# usb-cuter.net
KiCad netlist of a schematic drawn in Altium Designer
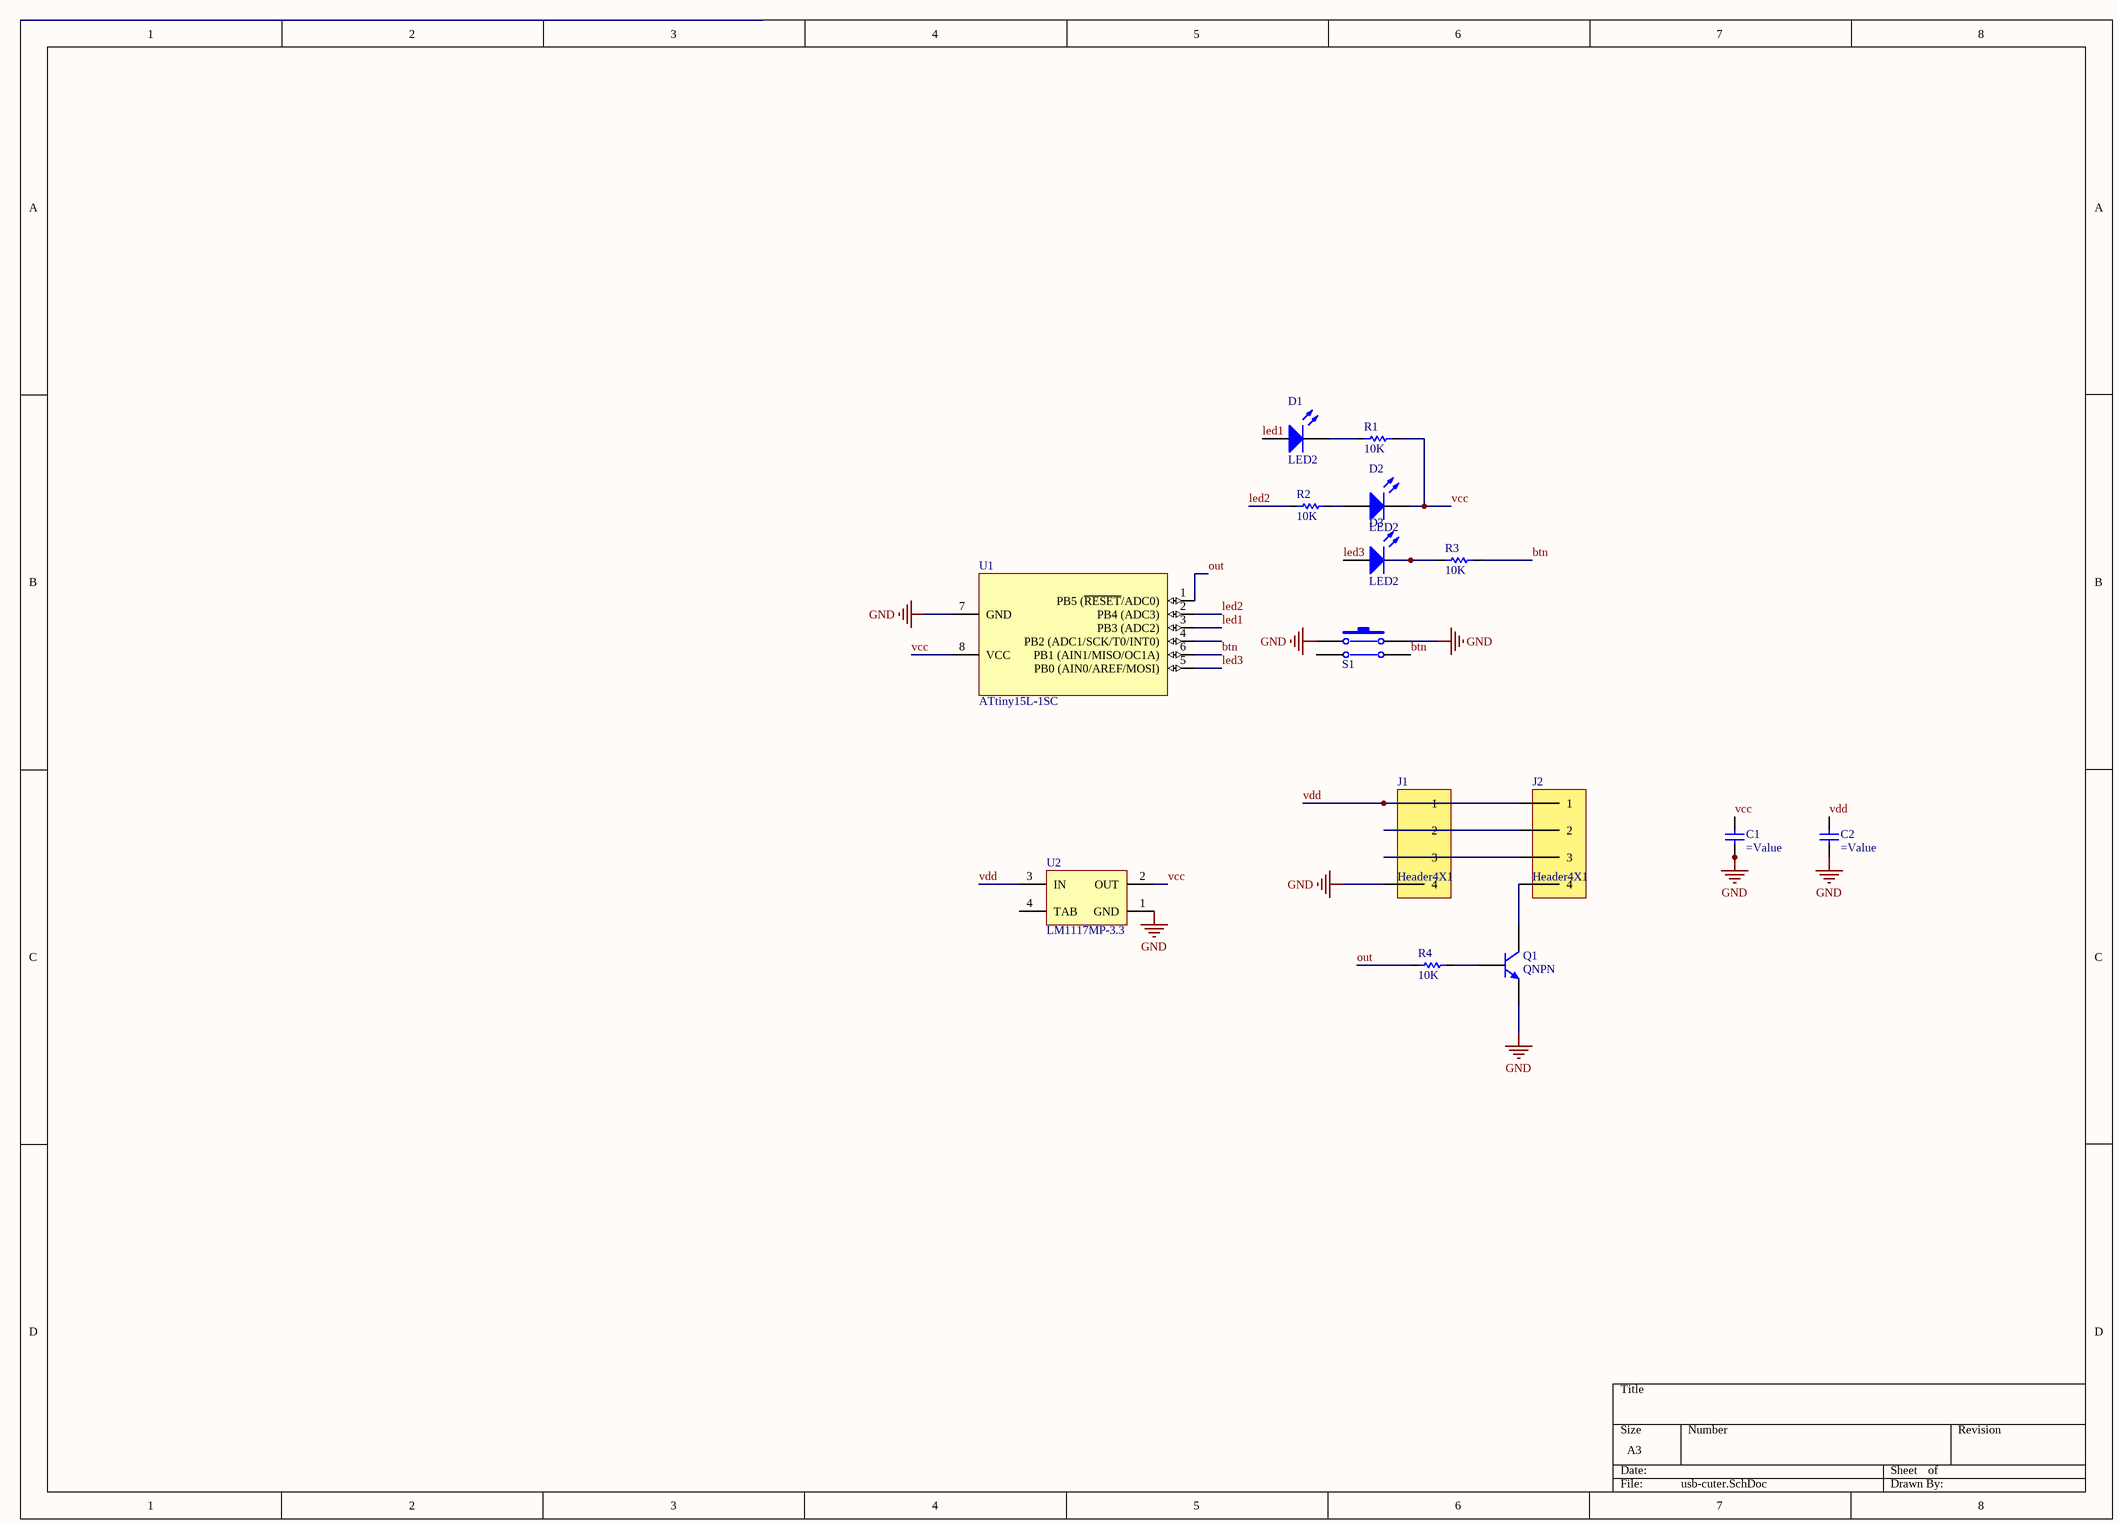
[diagram p0: usb-cuter.SchDoc]

(export (version "E")
  (design (tool "Eeschema 10.0.6"))
  (components
    (comp (ref "C1")
      (value "~")
      (footprint "CAP 0805")
      (description "Capacitor")
      (libsource (lib "AltiumLib1") (part "Capacitor"))
    )
    (comp (ref "C2")
      (value "~")
      (footprint "CAP 0805")
      (description "Capacitor")
      (libsource (lib "AltiumLib1") (part "Capacitor"))
    )
    (comp (ref "D1")
      (value "LED2")
      (footprint "3.2X1.6X1.1")
      (description "Typical RED, GREEN, YELLOW, AMBER GaAs LED")
      (fields (field (name "PUBLISHER") "Altium Limited"))
      (libsource (lib "Miscellaneous Devices") (part "LED2"))
    )
    (comp (ref "D2")
      (value "LED2")
      (footprint "3.2X1.6X1.1")
      (description "Typical RED, GREEN, YELLOW, AMBER GaAs LED")
      (fields (field (name "PUBLISHER") "Altium Limited"))
      (libsource (lib "Miscellaneous Devices") (part "LED2"))
    )
    (comp (ref "D3")
      (value "LED2")
      (footprint "3.2X1.6X1.1")
      (description "Typical RED, GREEN, YELLOW, AMBER GaAs LED")
      (fields (field (name "PUBLISHER") "Altium Limited"))
      (libsource (lib "Miscellaneous Devices") (part "LED2"))
    )
    (comp (ref "J1")
      (value "Header4X1")
      (footprint "HEADER 4X1")
      (libsource (lib "AltiumLib1") (part "Header4X1"))
    )
    (comp (ref "J2")
      (value "Header4X1")
      (footprint "HEADER 4X1")
      (libsource (lib "AltiumLib1") (part "Header4X1"))
    )
    (comp (ref "Q1")
      (value "QNPN")
      (footprint "SOT-23B_L")
      (description "NPN Bipolar Transistor")
      (fields (field (name "PUBLISHER") "Altium Limited"))
      (libsource (lib "Miscellaneous Devices") (part "QNPN"))
    )
    (comp (ref "R1")
      (value "10K")
      (footprint "RES 0805 (2012X06L)")
      (description "Resistor")
      (fields (field (name "TOLERANCE") "5%") (field (name "POWER") "1/4 W"))
      (libsource (lib "AltiumLib1") (part "Resistor"))
    )
    (comp (ref "R2")
      (value "10K")
      (footprint "RES 0805 (2012X06L)")
      (description "Resistor")
      (fields (field (name "TOLERANCE") "5%") (field (name "POWER") "1/4 W"))
      (libsource (lib "AltiumLib1") (part "Resistor"))
    )
    (comp (ref "R3")
      (value "10K")
      (footprint "RES 0805 (2012X06L)")
      (description "Resistor")
      (fields (field (name "TOLERANCE") "5%") (field (name "POWER") "1/4 W"))
      (libsource (lib "AltiumLib1") (part "Resistor"))
    )
    (comp (ref "R4")
      (value "10K")
      (footprint "RES 0805 (2012X06L)")
      (description "Resistor")
      (fields (field (name "TOLERANCE") "5%") (field (name "POWER") "1/4 W"))
      (libsource (lib "AltiumLib1") (part "Resistor"))
    )
    (comp (ref "S1")
      (value "PUSH BUTTON DOUBLE")
      (footprint "PUSH BUTTON")
      (description "Switch")
      (libsource (lib "AltiumLib1") (part "PUSH BUTTON DOUBLE"))
    )
    (comp (ref "U1")
      (value "ATtiny15L-1SC")
      (footprint "8S2_N")
      (description "8-Bit AVR Microcontroller with 1K Byte of Flash Memory")
      (fields (field (name "PUBLISHER") "Altium Limited"))
      (libsource (lib "Atmel Microcontroller 8-Bit AVR") (part "ATtiny15L-1SC"))
    )
    (comp (ref "U2")
      (value "LM1117MP-3.3")
      (footprint "Miscellaneous Devices:SOT89L")
      (description "800mA Low-Dropout Linear Regulator")
      (fields
        (field (name "MANUFACTURER") "National Semiconductor")
        (field (name "DIGIKEYPARTNUMBER") "LM1117MP-3.3CT-ND")
        (field (name "PUBLISHER") "Altium Limited")
      )
      (libsource (lib "NSC LDO") (part "LM1117MP-3.3"))
    )
  )
  (nets
    (net (code "1") (name "/btn") (class "Default")
      (node (ref "R3") (pin "2") (pinfunction "2_2") (pintype "passive"))
      (node (ref "S1") (pin "4") (pinfunction "4_4") (pintype "passive"))
      (node (ref "U1") (pin "6") (pinfunction "PB1_(AIN1/MISO/OC1A)_6") (pintype "bidirectional"))
    )
    (net (code "2") (name "/led1") (class "Default")
      (node (ref "D1") (pin "1") (pinfunction "A_1") (pintype "passive"))
      (node (ref "U1") (pin "3") (pinfunction "PB3_(ADC2)_3") (pintype "bidirectional"))
    )
    (net (code "3") (name "/led2") (class "Default")
      (node (ref "R2") (pin "2") (pinfunction "2_2") (pintype "passive"))
      (node (ref "U1") (pin "2") (pinfunction "PB4_(ADC3)_2") (pintype "bidirectional"))
    )
    (net (code "4") (name "/led3") (class "Default")
      (node (ref "D3") (pin "1") (pinfunction "A_1") (pintype "passive"))
      (node (ref "U1") (pin "5") (pinfunction "PB0_(AIN0/AREF/MOSI)_5") (pintype "bidirectional"))
    )
    (net (code "5") (name "/out") (class "Default")
      (node (ref "R4") (pin "1") (pinfunction "1_1") (pintype "passive"))
      (node (ref "U1") (pin "1") (pinfunction "PB5_(~{RESET}/ADC0)_1") (pintype "bidirectional"))
    )
    (net (code "6") (name "/vcc") (class "Default")
      (node (ref "C1") (pin "2") (pinfunction "-_2") (pintype "passive"))
      (node (ref "D2") (pin "2") (pinfunction "K_2") (pintype "passive"))
      (node (ref "R1") (pin "1") (pinfunction "1_1") (pintype "passive"))
      (node (ref "U1") (pin "8") (pinfunction "VCC_8") (pintype "power_in"))
      (node (ref "U2") (pin "2") (pinfunction "OUT_2") (pintype "power_in"))
    )
    (net (code "7") (name "/vdd") (class "Default")
      (node (ref "C2") (pin "2") (pinfunction "-_2") (pintype "passive"))
      (node (ref "J1") (pin "1") (pinfunction "1_1") (pintype "passive"))
      (node (ref "J2") (pin "1") (pinfunction "1_1") (pintype "passive"))
      (node (ref "U2") (pin "3") (pinfunction "IN_3") (pintype "power_in"))
    )
    (net (code "8") (name "GND") (class "Default")
      (node (ref "C1") (pin "1") (pinfunction "+_1") (pintype "passive"))
      (node (ref "C2") (pin "1") (pinfunction "+_1") (pintype "passive"))
      (node (ref "J1") (pin "4") (pinfunction "4_4") (pintype "passive"))
      (node (ref "Q1") (pin "3") (pinfunction "E_3") (pintype "passive"))
      (node (ref "S1") (pin "1") (pinfunction "1_1") (pintype "passive"))
      (node (ref "S1") (pin "2") (pinfunction "2_2") (pintype "passive"))
      (node (ref "U1") (pin "7") (pinfunction "GND_7") (pintype "power_in"))
      (node (ref "U2") (pin "1") (pinfunction "GND_1") (pintype "power_in"))
    )
    (net (code "9") (name "Net-(D1-K)") (class "Default")
      (node (ref "D1") (pin "2") (pinfunction "K_2") (pintype "passive"))
      (node (ref "R1") (pin "2") (pinfunction "2_2") (pintype "passive"))
    )
    (net (code "10") (name "Net-(D2-A)") (class "Default")
      (node (ref "D2") (pin "1") (pinfunction "A_1") (pintype "passive"))
      (node (ref "R2") (pin "1") (pinfunction "1_1") (pintype "passive"))
    )
    (net (code "11") (name "Net-(D3-K)") (class "Default")
      (node (ref "D3") (pin "2") (pinfunction "K_2") (pintype "passive"))
      (node (ref "R3") (pin "1") (pinfunction "1_1") (pintype "passive"))
    )
    (net (code "12") (name "Net-(J1-Pad2)") (class "Default")
      (node (ref "J1") (pin "2") (pinfunction "2_2") (pintype "passive"))
      (node (ref "J2") (pin "2") (pinfunction "2_2") (pintype "passive"))
    )
    (net (code "13") (name "Net-(J1-Pad3)") (class "Default")
      (node (ref "J1") (pin "3") (pinfunction "3_3") (pintype "passive"))
      (node (ref "J2") (pin "3") (pinfunction "3_3") (pintype "passive"))
    )
    (net (code "14") (name "Net-(Q1-B)") (class "Default")
      (node (ref "Q1") (pin "2") (pinfunction "B_2") (pintype "passive"))
      (node (ref "R4") (pin "2") (pinfunction "2_2") (pintype "passive"))
    )
    (net (code "15") (name "Net-(Q1-C)") (class "Default")
      (node (ref "J2") (pin "4") (pinfunction "4_4") (pintype "passive"))
      (node (ref "Q1") (pin "1") (pinfunction "C_1") (pintype "passive"))
    )
    (net (code "16") (name "unconnected-(S1-Pad3)") (class "Default")
      (node (ref "S1") (pin "3") (pinfunction "3_3") (pintype "passive"))
    )
    (net (code "17") (name "unconnected-(U1-PB2_(ADC1{slash}SCK{slash}T0{slash}INT0)-Pad4)") (class "Default")
      (node (ref "U1") (pin "4") (pinfunction "PB2_(ADC1/SCK/T0/INT0)_4") (pintype "bidirectional"))
    )
    (net (code "18") (name "unconnected-(U2-TAB-Pad4)") (class "Default")
      (node (ref "U2") (pin "4") (pinfunction "TAB_4") (pintype "power_in"))
    )
  )
)
